# Main.net
KiCad netlist of a schematic drawn in EAGLE
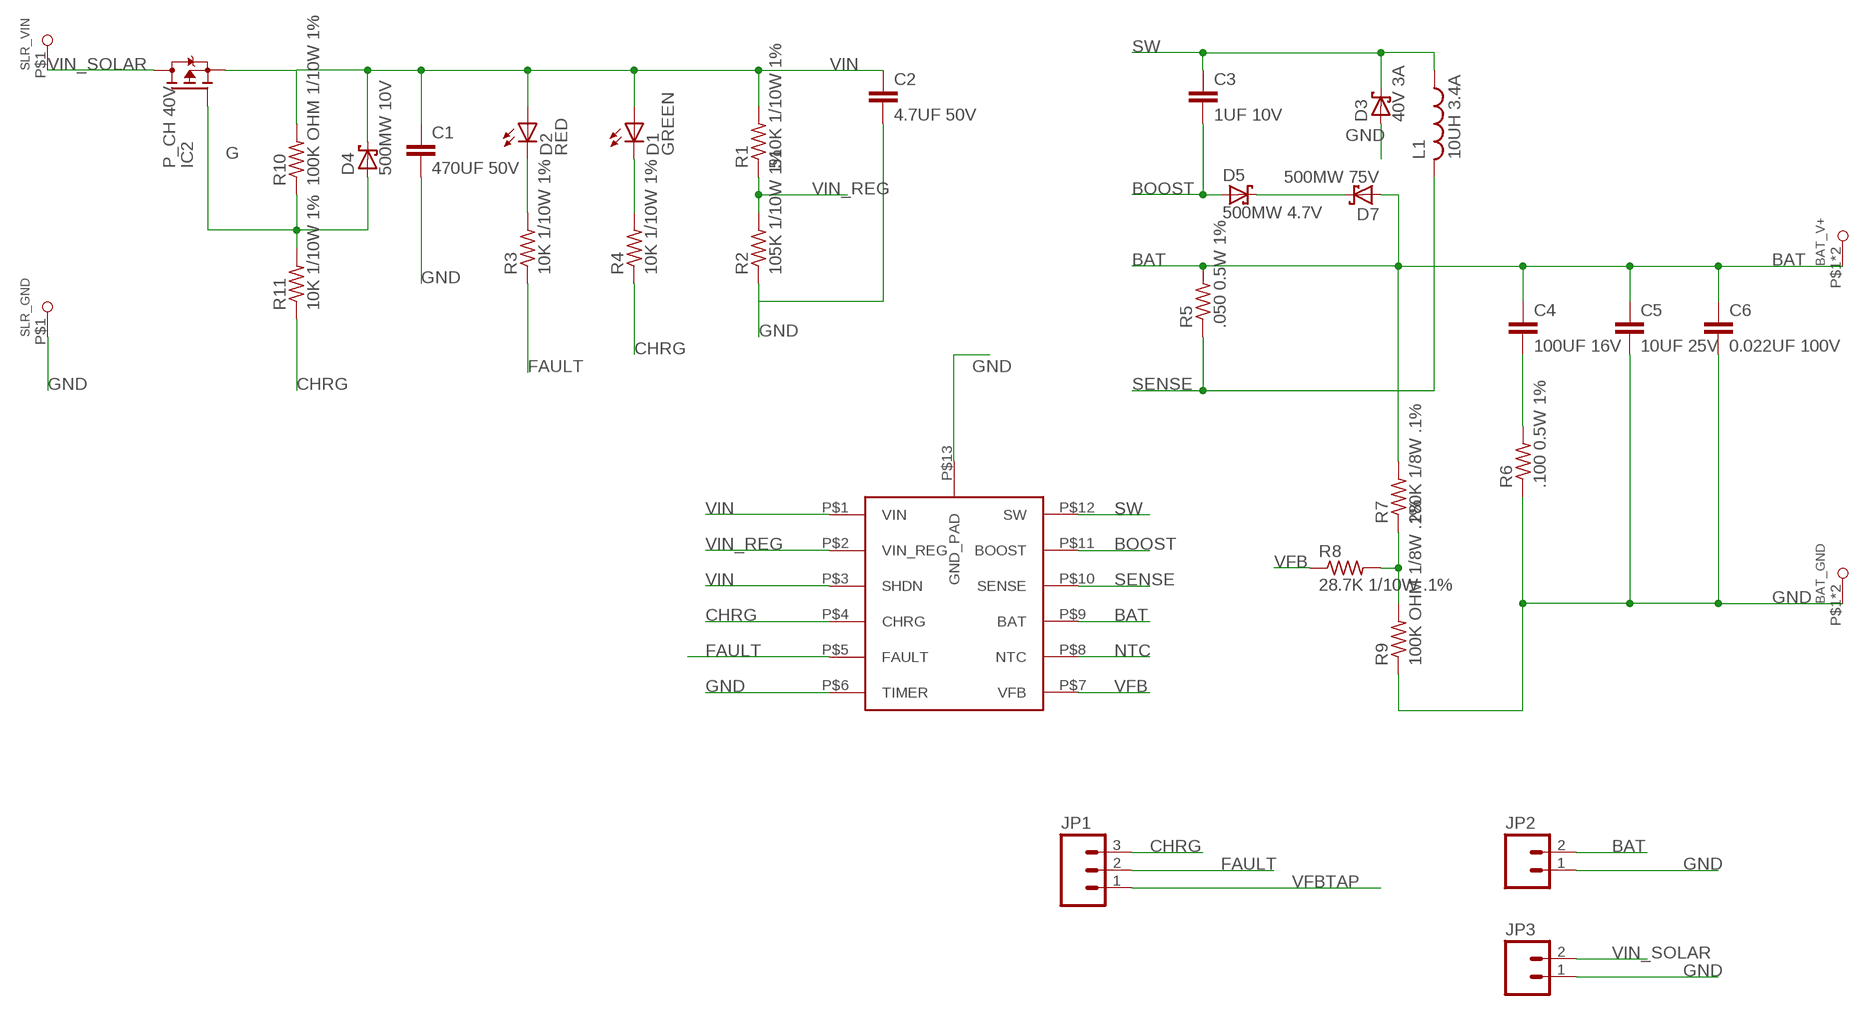
[diagram p0: schematic, sheet 1]

(export (version "E")
  (design (tool "Eeschema 10.0.6"))
  (components
    (comp (ref "BAT_GND")
      (value "LARGE_PADMED_PAD_PAIR")
      (footprint "eagle-import:MEDIUM_PAD_PAIR")
      (libsource (lib "eagle-import") (part "LARGE_PADMED_PAD_PAIR"))
    )
    (comp (ref "BAT_V+")
      (value "LARGE_PADMED_PAD_PAIR")
      (footprint "eagle-import:MEDIUM_PAD_PAIR")
      (libsource (lib "eagle-import") (part "LARGE_PADMED_PAD_PAIR"))
    )
    (comp (ref "C1")
      (value "470UF 50V")
      (footprint "eagle-import:5X5_CAP_HOLES")
      (libsource (lib "eagle-import") (part "SK471M050ST_(470µF_CAP)UPRIGHT_THROUGHHOLE"))
    )
    (comp (ref "C2")
      (value "4.7UF 50V")
      (footprint "eagle-import:C1210")
      (libsource (lib "eagle-import") (part "C-EUC1210"))
    )
    (comp (ref "C3")
      (value "1UF 10V")
      (footprint "eagle-import:C0805")
      (libsource (lib "eagle-import") (part "C-EUC0805"))
    )
    (comp (ref "C4")
      (value "100UF 16V")
      (footprint "eagle-import:C1210")
      (libsource (lib "eagle-import") (part "C-EUC1210"))
    )
    (comp (ref "C5")
      (value "10UF 25V")
      (footprint "eagle-import:C1210")
      (libsource (lib "eagle-import") (part "C-EUC1210"))
    )
    (comp (ref "C6")
      (value "0.022UF 100V")
      (footprint "eagle-import:C0805")
      (libsource (lib "eagle-import") (part "C-EUC0805"))
    )
    (comp (ref "D1")
      (value "GREEN")
      (footprint "eagle-import:SML0603")
      (libsource (lib "eagle-import") (part "LEDSML0603"))
    )
    (comp (ref "D2")
      (value "RED")
      (footprint "eagle-import:SML0603")
      (libsource (lib "eagle-import") (part "LEDSML0603"))
    )
    (comp (ref "D3")
      (value "40V 3A")
      (footprint "eagle-import:SMC")
      (libsource (lib "eagle-import") (part "SCHOTTKY-DIODESMC"))
    )
    (comp (ref "D4")
      (value "500MW 10V")
      (footprint "eagle-import:MINIMELF")
      (libsource (lib "eagle-import") (part "DIODE_MINIMELF"))
    )
    (comp (ref "D5")
      (value "500MW 4.7V")
      (footprint "eagle-import:MINIMELF")
      (libsource (lib "eagle-import") (part "DIODE_MINIMELF"))
    )
    (comp (ref "D7")
      (value "500MW 75V")
      (footprint "eagle-import:MINIMELF")
      (libsource (lib "eagle-import") (part "DIODE_MINIMELF"))
    )
    (comp (ref "IC1")
      (value "LT3652MSE-12-MIGHT-BE-HAND-DOOABLE")
      (footprint "eagle-import:MSE_12_HANDSOLDERABLE")
      (libsource (lib "eagle-import") (part "LT3652MSE-12-MIGHT-BE-HAND-DOOABLE"))
    )
    (comp (ref "IC2")
      (value "P_CH 40V")
      (footprint "eagle-import:SO-8_SOIC8")
      (libsource (lib "eagle-import") (part "MOSFET_P"))
    )
    (comp (ref "JP1")
      (value "M03LOCK")
      (footprint "eagle-import:1X03_LOCK")
      (libsource (lib "eagle-import") (part "M03LOCK"))
    )
    (comp (ref "JP2")
      (value "M02LOCK")
      (footprint "eagle-import:1X02_LOCK")
      (libsource (lib "eagle-import") (part "M02LOCK"))
    )
    (comp (ref "JP3")
      (value "M02LOCK")
      (footprint "eagle-import:1X02_LOCK")
      (libsource (lib "eagle-import") (part "M02LOCK"))
    )
    (comp (ref "L1")
      (value "10UH 3.4A")
      (footprint "eagle-import:ECOS_INDUCTOR_SMT")
      (libsource (lib "eagle-import") (part "INDUCTOR"))
    )
    (comp (ref "R1")
      (value "510K 1/10W 1%")
      (footprint "eagle-import:R0603")
      (libsource (lib "eagle-import") (part "R-US_R0603"))
    )
    (comp (ref "R2")
      (value "105K 1/10W 1%")
      (footprint "eagle-import:R0603")
      (libsource (lib "eagle-import") (part "R-US_R0603"))
    )
    (comp (ref "R3")
      (value "10K 1/10W 1%")
      (footprint "eagle-import:R0603")
      (libsource (lib "eagle-import") (part "R-US_R0603"))
    )
    (comp (ref "R4")
      (value "10K 1/10W 1%")
      (footprint "eagle-import:R0603")
      (libsource (lib "eagle-import") (part "R-US_R0603"))
    )
    (comp (ref "R5")
      (value ".050 0.5W 1%")
      (footprint "eagle-import:R1206")
      (libsource (lib "eagle-import") (part "R-US_R1206"))
    )
    (comp (ref "R6")
      (value ".100 0.5W 1%")
      (footprint "eagle-import:R1206")
      (libsource (lib "eagle-import") (part "R-US_R1206"))
    )
    (comp (ref "R7")
      (value "280K 1/8W .1%")
      (footprint "eagle-import:R0805")
      (libsource (lib "eagle-import") (part "R-US_R0805"))
    )
    (comp (ref "R8")
      (value "28.7K 1/10W .1%")
      (footprint "eagle-import:R0603")
      (libsource (lib "eagle-import") (part "R-US_R0603"))
    )
    (comp (ref "R9")
      (value "100K OHM 1/8W .1%")
      (footprint "eagle-import:R0805")
      (libsource (lib "eagle-import") (part "R-US_R0805"))
    )
    (comp (ref "R10")
      (value "100K OHM 1/10W 1%")
      (footprint "eagle-import:R0603")
      (libsource (lib "eagle-import") (part "R-US_R0603"))
    )
    (comp (ref "R11")
      (value "10K 1/10W 1%")
      (footprint "eagle-import:R0603")
      (libsource (lib "eagle-import") (part "R-US_R0603"))
    )
    (comp (ref "SLR_GND")
      (value "LARGE_PADMED_PAD")
      (footprint "eagle-import:MEDIUM_PAD")
      (libsource (lib "eagle-import") (part "LARGE_PADMED_PAD"))
    )
    (comp (ref "SLR_VIN")
      (value "LARGE_PADMED_PAD")
      (footprint "eagle-import:MEDIUM_PAD")
      (libsource (lib "eagle-import") (part "LARGE_PADMED_PAD"))
    )
  )
  (nets
    (net (code "1") (name "/BAT") (class "Default")
      (node (ref "BAT_V+") (pin "P$1") (pinfunction "P1_P$1") (pintype "bidirectional"))
      (node (ref "BAT_V+") (pin "P$2") (pinfunction "P1_P$2") (pintype "bidirectional"))
      (node (ref "C4") (pin "1") (pinfunction "1_1") (pintype "passive"))
      (node (ref "C5") (pin "1") (pinfunction "1_1") (pintype "passive"))
      (node (ref "C6") (pin "1") (pinfunction "1_1") (pintype "passive"))
      (node (ref "D7") (pin "P$1") (pinfunction "A_P$1") (pintype "passive"))
      (node (ref "IC1") (pin "P$9") (pinfunction "BAT_P$9") (pintype "bidirectional"))
      (node (ref "JP2") (pin "2") (pinfunction "2_2") (pintype "passive"))
      (node (ref "R5") (pin "2") (pinfunction "2_2") (pintype "passive"))
      (node (ref "R7") (pin "2") (pinfunction "2_2") (pintype "passive"))
    )
    (net (code "2") (name "/BOOST") (class "Default")
      (node (ref "C3") (pin "2") (pinfunction "2_2") (pintype "passive"))
      (node (ref "D5") (pin "P$1") (pinfunction "A_P$1") (pintype "passive"))
      (node (ref "IC1") (pin "P$11") (pinfunction "BOOST_P$11") (pintype "bidirectional"))
    )
    (net (code "3") (name "/CHRG") (class "Default")
      (node (ref "IC1") (pin "P$4") (pinfunction "CHRG_P$4") (pintype "bidirectional"))
      (node (ref "JP1") (pin "3") (pinfunction "3_3") (pintype "passive"))
      (node (ref "R11") (pin "1") (pinfunction "1_1") (pintype "passive"))
      (node (ref "R4") (pin "1") (pinfunction "1_1") (pintype "passive"))
    )
    (net (code "4") (name "/FAULT") (class "Default")
      (node (ref "IC1") (pin "P$5") (pinfunction "FAULT_P$5") (pintype "bidirectional"))
      (node (ref "JP1") (pin "2") (pinfunction "2_2") (pintype "passive"))
      (node (ref "R3") (pin "1") (pinfunction "1_1") (pintype "passive"))
    )
    (net (code "5") (name "/G") (class "Default")
      (node (ref "D4") (pin "P$1") (pinfunction "A_P$1") (pintype "passive"))
      (node (ref "IC2") (pin "4") (pinfunction "G_4") (pintype "passive"))
      (node (ref "R10") (pin "1") (pinfunction "1_1") (pintype "passive"))
      (node (ref "R11") (pin "2") (pinfunction "2_2") (pintype "passive"))
    )
    (net (code "6") (name "/GND") (class "Default")
      (node (ref "BAT_GND") (pin "P$1") (pinfunction "P1_P$1") (pintype "bidirectional"))
      (node (ref "BAT_GND") (pin "P$2") (pinfunction "P1_P$2") (pintype "bidirectional"))
      (node (ref "C1") (pin "P$2") (pinfunction "2_P$2") (pintype "passive"))
      (node (ref "C2") (pin "2") (pinfunction "2_2") (pintype "passive"))
      (node (ref "C5") (pin "2") (pinfunction "2_2") (pintype "passive"))
      (node (ref "C6") (pin "2") (pinfunction "2_2") (pintype "passive"))
      (node (ref "D3") (pin "A") (pinfunction "A_A") (pintype "passive"))
      (node (ref "IC1") (pin "P$13") (pinfunction "GND_PAD_P$13") (pintype "bidirectional"))
      (node (ref "IC1") (pin "P$6") (pinfunction "TIMER_P$6") (pintype "bidirectional"))
      (node (ref "JP2") (pin "1") (pinfunction "1_1") (pintype "passive"))
      (node (ref "JP3") (pin "1") (pinfunction "1_1") (pintype "passive"))
      (node (ref "R2") (pin "1") (pinfunction "1_1") (pintype "passive"))
      (node (ref "R6") (pin "1") (pinfunction "1_1") (pintype "passive"))
      (node (ref "R9") (pin "1") (pinfunction "1_1") (pintype "passive"))
      (node (ref "SLR_GND") (pin "P$1") (pinfunction "P1_P$1") (pintype "bidirectional"))
    )
    (net (code "7") (name "/NTC") (class "Default")
      (node (ref "IC1") (pin "P$8") (pinfunction "NTC_P$8") (pintype "bidirectional"))
    )
    (net (code "8") (name "/SENSE") (class "Default")
      (node (ref "IC1") (pin "P$10") (pinfunction "SENSE_P$10") (pintype "bidirectional"))
      (node (ref "L1") (pin "P$2") (pinfunction "2_P$2") (pintype "passive"))
      (node (ref "R5") (pin "1") (pinfunction "1_1") (pintype "passive"))
    )
    (net (code "9") (name "/SW") (class "Default")
      (node (ref "C3") (pin "1") (pinfunction "1_1") (pintype "passive"))
      (node (ref "D3") (pin "C") (pinfunction "C_C") (pintype "passive"))
      (node (ref "IC1") (pin "P$12") (pinfunction "SW_P$12") (pintype "bidirectional"))
      (node (ref "L1") (pin "P$1") (pinfunction "1_P$1") (pintype "passive"))
    )
    (net (code "10") (name "/VFB") (class "Default")
      (node (ref "IC1") (pin "P$7") (pinfunction "VFB_P$7") (pintype "bidirectional"))
      (node (ref "R8") (pin "1") (pinfunction "1_1") (pintype "passive"))
    )
    (net (code "11") (name "/VFBTAP") (class "Default")
      (node (ref "JP1") (pin "1") (pinfunction "1_1") (pintype "passive"))
      (node (ref "R7") (pin "1") (pinfunction "1_1") (pintype "passive"))
      (node (ref "R8") (pin "2") (pinfunction "2_2") (pintype "passive"))
      (node (ref "R9") (pin "2") (pinfunction "2_2") (pintype "passive"))
    )
    (net (code "12") (name "/VIN") (class "Default")
      (node (ref "C1") (pin "P$1") (pinfunction "1_P$1") (pintype "passive"))
      (node (ref "C2") (pin "1") (pinfunction "1_1") (pintype "passive"))
      (node (ref "D1") (pin "A") (pinfunction "A_A") (pintype "passive"))
      (node (ref "D2") (pin "A") (pinfunction "A_A") (pintype "passive"))
      (node (ref "D4") (pin "P$2") (pinfunction "C_P$2") (pintype "passive"))
      (node (ref "IC1") (pin "P$1") (pinfunction "VIN_P$1") (pintype "bidirectional"))
      (node (ref "IC1") (pin "P$3") (pinfunction "SHDN_P$3") (pintype "bidirectional"))
      (node (ref "IC2") (pin "1") (pinfunction "S_1") (pintype "passive"))
      (node (ref "IC2") (pin "2") (pinfunction "S_2") (pintype "passive"))
      (node (ref "IC2") (pin "3") (pinfunction "S_3") (pintype "passive"))
      (node (ref "R1") (pin "2") (pinfunction "2_2") (pintype "passive"))
      (node (ref "R10") (pin "2") (pinfunction "2_2") (pintype "passive"))
    )
    (net (code "13") (name "/VIN_REG") (class "Default")
      (node (ref "IC1") (pin "P$2") (pinfunction "VIN_REG_P$2") (pintype "bidirectional"))
      (node (ref "R1") (pin "1") (pinfunction "1_1") (pintype "passive"))
      (node (ref "R2") (pin "2") (pinfunction "2_2") (pintype "passive"))
    )
    (net (code "14") (name "/VIN_SOLAR") (class "Default")
      (node (ref "IC2") (pin "5") (pinfunction "D_5") (pintype "passive"))
      (node (ref "IC2") (pin "6") (pinfunction "D_6") (pintype "passive"))
      (node (ref "IC2") (pin "7") (pinfunction "D_7") (pintype "passive"))
      (node (ref "IC2") (pin "8") (pinfunction "D_8") (pintype "passive"))
      (node (ref "JP3") (pin "2") (pinfunction "2_2") (pintype "passive"))
      (node (ref "SLR_VIN") (pin "P$1") (pinfunction "P1_P$1") (pintype "bidirectional"))
    )
    (net (code "15") (name "Net-(C4-Pad2)") (class "Default")
      (node (ref "C4") (pin "2") (pinfunction "2_2") (pintype "passive"))
      (node (ref "R6") (pin "2") (pinfunction "2_2") (pintype "passive"))
    )
    (net (code "16") (name "Net-(D1-PadC)") (class "Default")
      (node (ref "D1") (pin "C") (pinfunction "C_C") (pintype "passive"))
      (node (ref "R4") (pin "2") (pinfunction "2_2") (pintype "passive"))
    )
    (net (code "17") (name "Net-(D2-PadC)") (class "Default")
      (node (ref "D2") (pin "C") (pinfunction "C_C") (pintype "passive"))
      (node (ref "R3") (pin "2") (pinfunction "2_2") (pintype "passive"))
    )
    (net (code "18") (name "Net-(D5-C)") (class "Default")
      (node (ref "D5") (pin "P$2") (pinfunction "C_P$2") (pintype "passive"))
      (node (ref "D7") (pin "P$2") (pinfunction "C_P$2") (pintype "passive"))
    )
  )
)
